# relays_1-4.net
KiCad netlist of a schematic drawn in Altium Designer
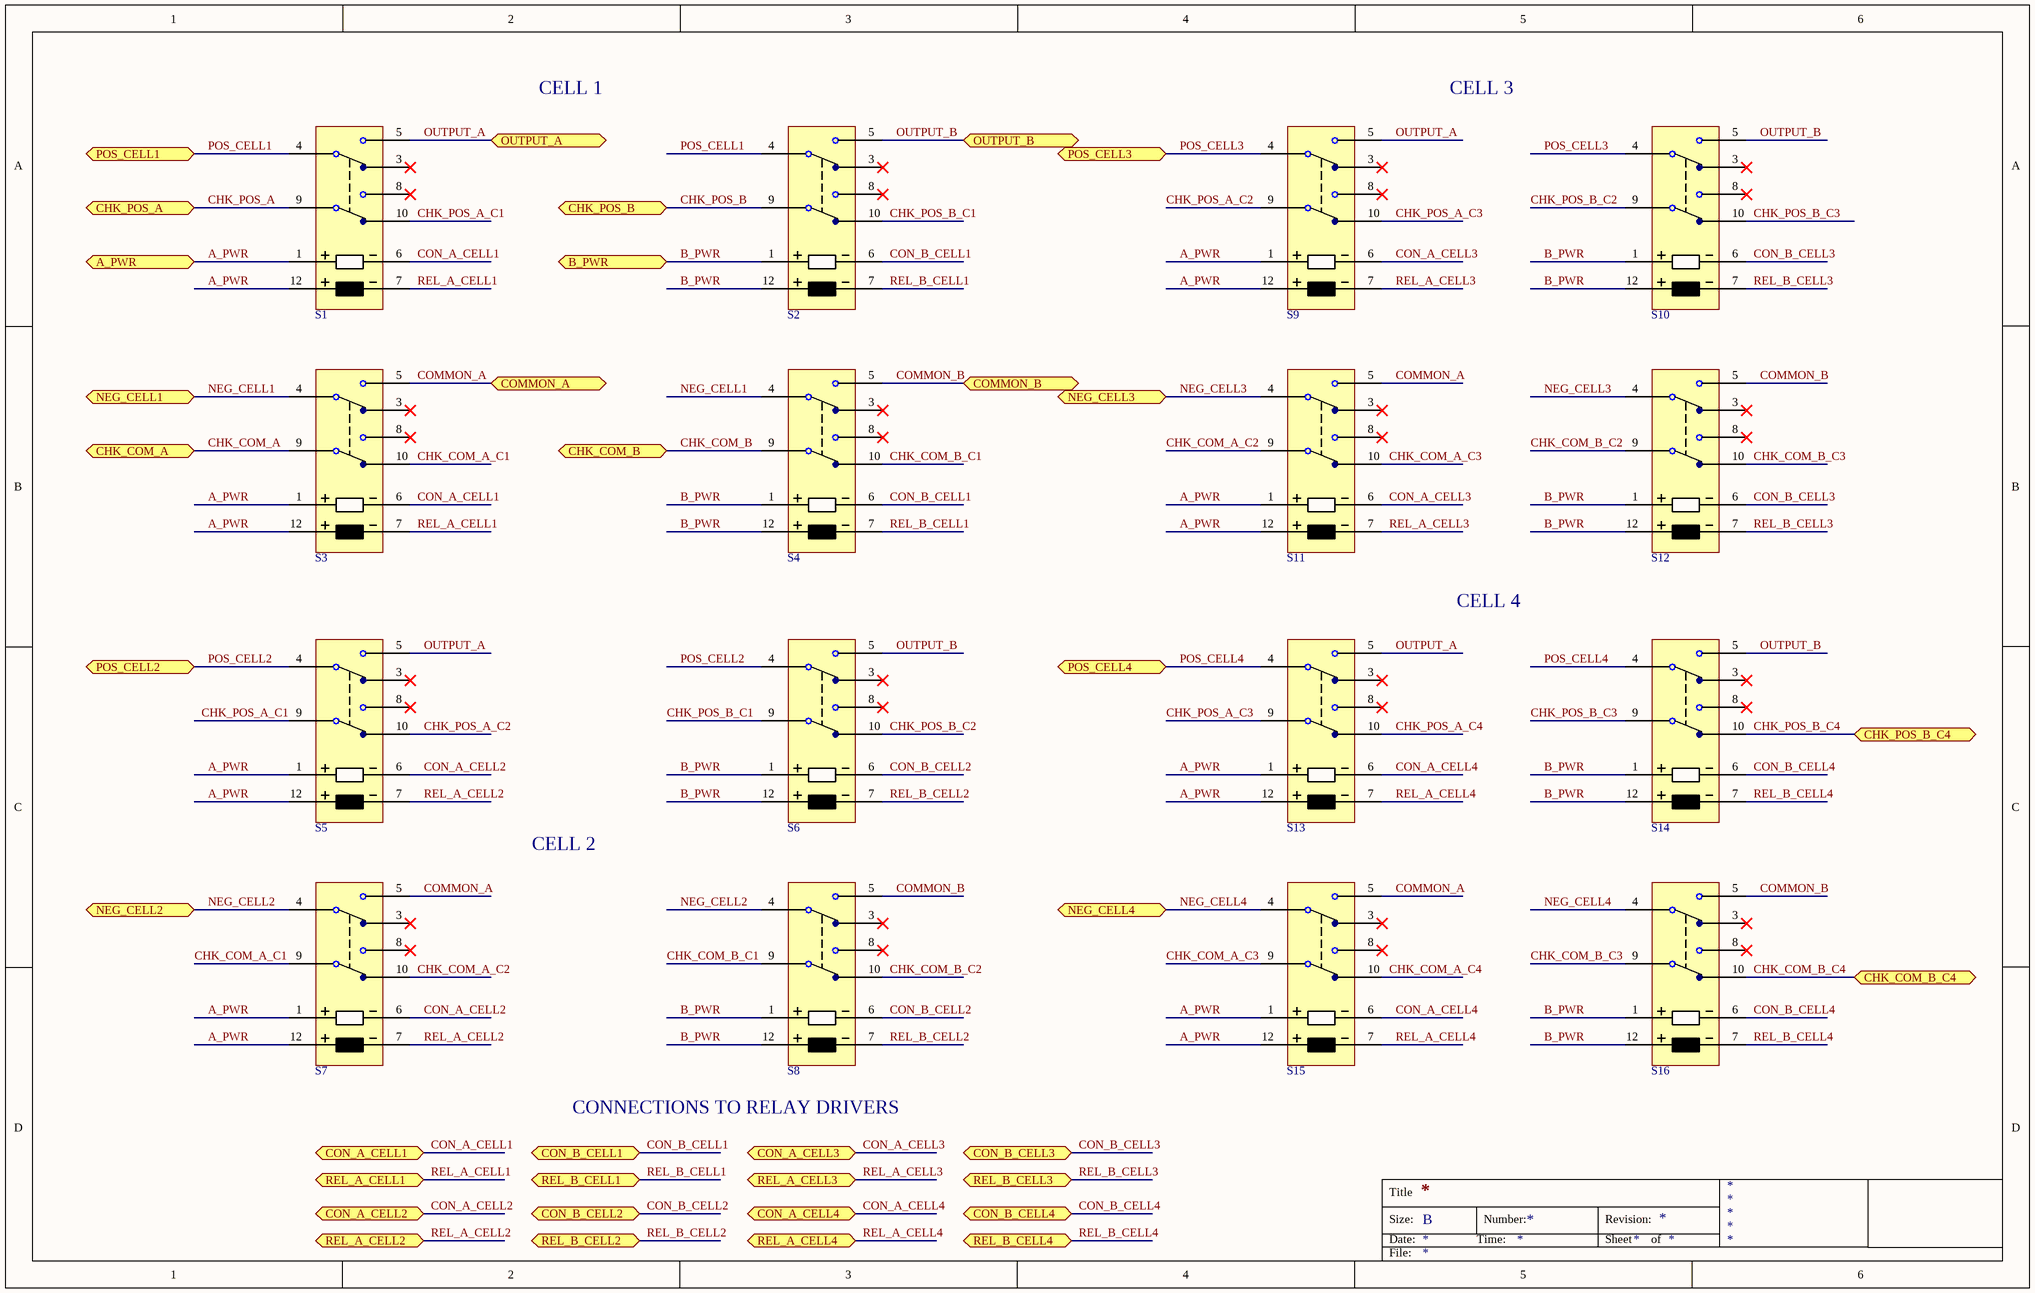
[diagram p0: relays_1-4.SchDoc]

(export (version "E")
  (design (tool "Eeschema 10.0.6"))
  (components
    (comp (ref "S1")
      (value "DPDT_RELAY_L2")
      (footprint "L2_RELAY")
      (description "RELAY GEN PURPOSE DPDT 1A 4.5V")
      (fields
        (field (name "MANUFACTURER") "Panasonic Electric Works")
        (field (name "MANUFACTURER PART NUMBER") "TXS2-L2-4.5V")
      )
      (libsource (lib "mechanart_oshw") (part "DPDT_RELAY_L2"))
    )
    (comp (ref "S2")
      (value "DPDT_RELAY_L2")
      (footprint "L2_RELAY")
      (description "RELAY GEN PURPOSE DPDT 1A 4.5V")
      (fields
        (field (name "MANUFACTURER") "Panasonic Electric Works")
        (field (name "MANUFACTURER PART NUMBER") "TXS2-L2-4.5V")
      )
      (libsource (lib "mechanart_oshw") (part "DPDT_RELAY_L2"))
    )
    (comp (ref "S3")
      (value "DPDT_RELAY_L2")
      (footprint "L2_RELAY")
      (description "RELAY GEN PURPOSE DPDT 1A 4.5V")
      (fields
        (field (name "MANUFACTURER") "Panasonic Electric Works")
        (field (name "MANUFACTURER PART NUMBER") "TXS2-L2-4.5V")
      )
      (libsource (lib "mechanart_oshw") (part "DPDT_RELAY_L2"))
    )
    (comp (ref "S4")
      (value "DPDT_RELAY_L2")
      (footprint "L2_RELAY")
      (description "RELAY GEN PURPOSE DPDT 1A 4.5V")
      (fields
        (field (name "MANUFACTURER") "Panasonic Electric Works")
        (field (name "MANUFACTURER PART NUMBER") "TXS2-L2-4.5V")
      )
      (libsource (lib "mechanart_oshw") (part "DPDT_RELAY_L2"))
    )
    (comp (ref "S5")
      (value "DPDT_RELAY_L2")
      (footprint "L2_RELAY")
      (description "RELAY GEN PURPOSE DPDT 1A 4.5V")
      (fields
        (field (name "MANUFACTURER") "Panasonic Electric Works")
        (field (name "MANUFACTURER PART NUMBER") "TXS2-L2-4.5V")
      )
      (libsource (lib "mechanart_oshw") (part "DPDT_RELAY_L2"))
    )
    (comp (ref "S6")
      (value "DPDT_RELAY_L2")
      (footprint "L2_RELAY")
      (description "RELAY GEN PURPOSE DPDT 1A 4.5V")
      (fields
        (field (name "MANUFACTURER") "Panasonic Electric Works")
        (field (name "MANUFACTURER PART NUMBER") "TXS2-L2-4.5V")
      )
      (libsource (lib "mechanart_oshw") (part "DPDT_RELAY_L2"))
    )
    (comp (ref "S7")
      (value "DPDT_RELAY_L2")
      (footprint "L2_RELAY")
      (description "RELAY GEN PURPOSE DPDT 1A 4.5V")
      (fields
        (field (name "MANUFACTURER") "Panasonic Electric Works")
        (field (name "MANUFACTURER PART NUMBER") "TXS2-L2-4.5V")
      )
      (libsource (lib "mechanart_oshw") (part "DPDT_RELAY_L2"))
    )
    (comp (ref "S8")
      (value "DPDT_RELAY_L2")
      (footprint "L2_RELAY")
      (description "RELAY GEN PURPOSE DPDT 1A 4.5V")
      (fields
        (field (name "MANUFACTURER") "Panasonic Electric Works")
        (field (name "MANUFACTURER PART NUMBER") "TXS2-L2-4.5V")
      )
      (libsource (lib "mechanart_oshw") (part "DPDT_RELAY_L2"))
    )
    (comp (ref "S9")
      (value "DPDT_RELAY_L2")
      (footprint "L2_RELAY")
      (description "RELAY GEN PURPOSE DPDT 1A 4.5V")
      (fields
        (field (name "MANUFACTURER") "Panasonic Electric Works")
        (field (name "MANUFACTURER PART NUMBER") "TXS2-L2-4.5V")
      )
      (libsource (lib "mechanart_oshw") (part "DPDT_RELAY_L2"))
    )
    (comp (ref "S10")
      (value "DPDT_RELAY_L2")
      (footprint "L2_RELAY")
      (description "RELAY GEN PURPOSE DPDT 1A 4.5V")
      (fields
        (field (name "MANUFACTURER") "Panasonic Electric Works")
        (field (name "MANUFACTURER PART NUMBER") "TXS2-L2-4.5V")
      )
      (libsource (lib "mechanart_oshw") (part "DPDT_RELAY_L2"))
    )
    (comp (ref "S11")
      (value "DPDT_RELAY_L2")
      (footprint "L2_RELAY")
      (description "RELAY GEN PURPOSE DPDT 1A 4.5V")
      (fields
        (field (name "MANUFACTURER") "Panasonic Electric Works")
        (field (name "MANUFACTURER PART NUMBER") "TXS2-L2-4.5V")
      )
      (libsource (lib "mechanart_oshw") (part "DPDT_RELAY_L2"))
    )
    (comp (ref "S12")
      (value "DPDT_RELAY_L2")
      (footprint "L2_RELAY")
      (description "RELAY GEN PURPOSE DPDT 1A 4.5V")
      (fields
        (field (name "MANUFACTURER") "Panasonic Electric Works")
        (field (name "MANUFACTURER PART NUMBER") "TXS2-L2-4.5V")
      )
      (libsource (lib "mechanart_oshw") (part "DPDT_RELAY_L2"))
    )
    (comp (ref "S13")
      (value "DPDT_RELAY_L2")
      (footprint "L2_RELAY")
      (description "RELAY GEN PURPOSE DPDT 1A 4.5V")
      (fields
        (field (name "MANUFACTURER") "Panasonic Electric Works")
        (field (name "MANUFACTURER PART NUMBER") "TXS2-L2-4.5V")
      )
      (libsource (lib "mechanart_oshw") (part "DPDT_RELAY_L2"))
    )
    (comp (ref "S14")
      (value "DPDT_RELAY_L2")
      (footprint "L2_RELAY")
      (description "RELAY GEN PURPOSE DPDT 1A 4.5V")
      (fields
        (field (name "MANUFACTURER") "Panasonic Electric Works")
        (field (name "MANUFACTURER PART NUMBER") "TXS2-L2-4.5V")
      )
      (libsource (lib "mechanart_oshw") (part "DPDT_RELAY_L2"))
    )
    (comp (ref "S15")
      (value "DPDT_RELAY_L2")
      (footprint "L2_RELAY")
      (description "RELAY GEN PURPOSE DPDT 1A 4.5V")
      (fields
        (field (name "MANUFACTURER") "Panasonic Electric Works")
        (field (name "MANUFACTURER PART NUMBER") "TXS2-L2-4.5V")
      )
      (libsource (lib "mechanart_oshw") (part "DPDT_RELAY_L2"))
    )
    (comp (ref "S16")
      (value "DPDT_RELAY_L2")
      (footprint "L2_RELAY")
      (description "RELAY GEN PURPOSE DPDT 1A 4.5V")
      (fields
        (field (name "MANUFACTURER") "Panasonic Electric Works")
        (field (name "MANUFACTURER PART NUMBER") "TXS2-L2-4.5V")
      )
      (libsource (lib "mechanart_oshw") (part "DPDT_RELAY_L2"))
    )
  )
  (nets
    (net (code "1") (name "/A_PWR") (class "Default")
      (node (ref "S1") (pin "1") (pinfunction "1_1") (pintype "passive"))
      (node (ref "S1") (pin "12") (pinfunction "12_12") (pintype "passive"))
      (node (ref "S11") (pin "1") (pinfunction "1_1") (pintype "passive"))
      (node (ref "S11") (pin "12") (pinfunction "12_12") (pintype "passive"))
      (node (ref "S13") (pin "1") (pinfunction "1_1") (pintype "passive"))
      (node (ref "S13") (pin "12") (pinfunction "12_12") (pintype "passive"))
      (node (ref "S15") (pin "1") (pinfunction "1_1") (pintype "passive"))
      (node (ref "S15") (pin "12") (pinfunction "12_12") (pintype "passive"))
      (node (ref "S3") (pin "1") (pinfunction "1_1") (pintype "passive"))
      (node (ref "S3") (pin "12") (pinfunction "12_12") (pintype "passive"))
      (node (ref "S5") (pin "1") (pinfunction "1_1") (pintype "passive"))
      (node (ref "S5") (pin "12") (pinfunction "12_12") (pintype "passive"))
      (node (ref "S7") (pin "1") (pinfunction "1_1") (pintype "passive"))
      (node (ref "S7") (pin "12") (pinfunction "12_12") (pintype "passive"))
      (node (ref "S9") (pin "1") (pinfunction "1_1") (pintype "passive"))
      (node (ref "S9") (pin "12") (pinfunction "12_12") (pintype "passive"))
    )
    (net (code "2") (name "/B_PWR") (class "Default")
      (node (ref "S10") (pin "1") (pinfunction "1_1") (pintype "passive"))
      (node (ref "S10") (pin "12") (pinfunction "12_12") (pintype "passive"))
      (node (ref "S12") (pin "1") (pinfunction "1_1") (pintype "passive"))
      (node (ref "S12") (pin "12") (pinfunction "12_12") (pintype "passive"))
      (node (ref "S14") (pin "1") (pinfunction "1_1") (pintype "passive"))
      (node (ref "S14") (pin "12") (pinfunction "12_12") (pintype "passive"))
      (node (ref "S16") (pin "1") (pinfunction "1_1") (pintype "passive"))
      (node (ref "S16") (pin "12") (pinfunction "12_12") (pintype "passive"))
      (node (ref "S2") (pin "1") (pinfunction "1_1") (pintype "passive"))
      (node (ref "S2") (pin "12") (pinfunction "12_12") (pintype "passive"))
      (node (ref "S4") (pin "1") (pinfunction "1_1") (pintype "passive"))
      (node (ref "S4") (pin "12") (pinfunction "12_12") (pintype "passive"))
      (node (ref "S6") (pin "1") (pinfunction "1_1") (pintype "passive"))
      (node (ref "S6") (pin "12") (pinfunction "12_12") (pintype "passive"))
      (node (ref "S8") (pin "1") (pinfunction "1_1") (pintype "passive"))
      (node (ref "S8") (pin "12") (pinfunction "12_12") (pintype "passive"))
    )
    (net (code "3") (name "/CHK_COM_A") (class "Default")
      (node (ref "S3") (pin "9") (pinfunction "9_9") (pintype "passive"))
    )
    (net (code "4") (name "/CHK_COM_A_C1") (class "Default")
      (node (ref "S3") (pin "10") (pinfunction "10_10") (pintype "passive"))
      (node (ref "S7") (pin "9") (pinfunction "9_9") (pintype "passive"))
    )
    (net (code "5") (name "/CHK_COM_A_C2") (class "Default")
      (node (ref "S11") (pin "9") (pinfunction "9_9") (pintype "passive"))
      (node (ref "S7") (pin "10") (pinfunction "10_10") (pintype "passive"))
    )
    (net (code "6") (name "/CHK_COM_A_C3") (class "Default")
      (node (ref "S11") (pin "10") (pinfunction "10_10") (pintype "passive"))
      (node (ref "S15") (pin "9") (pinfunction "9_9") (pintype "passive"))
    )
    (net (code "7") (name "/CHK_COM_A_C4") (class "Default")
      (node (ref "S15") (pin "10") (pinfunction "10_10") (pintype "passive"))
    )
    (net (code "8") (name "/CHK_COM_B") (class "Default")
      (node (ref "S4") (pin "9") (pinfunction "9_9") (pintype "passive"))
    )
    (net (code "9") (name "/CHK_COM_B_C1") (class "Default")
      (node (ref "S4") (pin "10") (pinfunction "10_10") (pintype "passive"))
      (node (ref "S8") (pin "9") (pinfunction "9_9") (pintype "passive"))
    )
    (net (code "10") (name "/CHK_COM_B_C2") (class "Default")
      (node (ref "S12") (pin "9") (pinfunction "9_9") (pintype "passive"))
      (node (ref "S8") (pin "10") (pinfunction "10_10") (pintype "passive"))
    )
    (net (code "11") (name "/CHK_COM_B_C3") (class "Default")
      (node (ref "S12") (pin "10") (pinfunction "10_10") (pintype "passive"))
      (node (ref "S16") (pin "9") (pinfunction "9_9") (pintype "passive"))
    )
    (net (code "12") (name "/CHK_COM_B_C4") (class "Default")
      (node (ref "S16") (pin "10") (pinfunction "10_10") (pintype "passive"))
    )
    (net (code "13") (name "/CHK_POS_A") (class "Default")
      (node (ref "S1") (pin "9") (pinfunction "9_9") (pintype "passive"))
    )
    (net (code "14") (name "/CHK_POS_A_C1") (class "Default")
      (node (ref "S1") (pin "10") (pinfunction "10_10") (pintype "passive"))
      (node (ref "S5") (pin "9") (pinfunction "9_9") (pintype "passive"))
    )
    (net (code "15") (name "/CHK_POS_A_C2") (class "Default")
      (node (ref "S5") (pin "10") (pinfunction "10_10") (pintype "passive"))
      (node (ref "S9") (pin "9") (pinfunction "9_9") (pintype "passive"))
    )
    (net (code "16") (name "/CHK_POS_A_C3") (class "Default")
      (node (ref "S13") (pin "9") (pinfunction "9_9") (pintype "passive"))
      (node (ref "S9") (pin "10") (pinfunction "10_10") (pintype "passive"))
    )
    (net (code "17") (name "/CHK_POS_A_C4") (class "Default")
      (node (ref "S13") (pin "10") (pinfunction "10_10") (pintype "passive"))
    )
    (net (code "18") (name "/CHK_POS_B") (class "Default")
      (node (ref "S2") (pin "9") (pinfunction "9_9") (pintype "passive"))
    )
    (net (code "19") (name "/CHK_POS_B_C1") (class "Default")
      (node (ref "S2") (pin "10") (pinfunction "10_10") (pintype "passive"))
      (node (ref "S6") (pin "9") (pinfunction "9_9") (pintype "passive"))
    )
    (net (code "20") (name "/CHK_POS_B_C2") (class "Default")
      (node (ref "S10") (pin "9") (pinfunction "9_9") (pintype "passive"))
      (node (ref "S6") (pin "10") (pinfunction "10_10") (pintype "passive"))
    )
    (net (code "21") (name "/CHK_POS_B_C3") (class "Default")
      (node (ref "S10") (pin "10") (pinfunction "10_10") (pintype "passive"))
      (node (ref "S14") (pin "9") (pinfunction "9_9") (pintype "passive"))
    )
    (net (code "22") (name "/CHK_POS_B_C4") (class "Default")
      (node (ref "S14") (pin "10") (pinfunction "10_10") (pintype "passive"))
    )
    (net (code "23") (name "/COMMON_A") (class "Default")
      (node (ref "S11") (pin "5") (pinfunction "5_5") (pintype "passive"))
      (node (ref "S15") (pin "5") (pinfunction "5_5") (pintype "passive"))
      (node (ref "S3") (pin "5") (pinfunction "5_5") (pintype "passive"))
      (node (ref "S7") (pin "5") (pinfunction "5_5") (pintype "passive"))
    )
    (net (code "24") (name "/COMMON_B") (class "Default")
      (node (ref "S12") (pin "5") (pinfunction "5_5") (pintype "passive"))
      (node (ref "S16") (pin "5") (pinfunction "5_5") (pintype "passive"))
      (node (ref "S4") (pin "5") (pinfunction "5_5") (pintype "passive"))
      (node (ref "S8") (pin "5") (pinfunction "5_5") (pintype "passive"))
    )
    (net (code "25") (name "/CON_A_CELL1") (class "Default")
      (node (ref "S1") (pin "6") (pinfunction "6_6") (pintype "passive"))
      (node (ref "S3") (pin "6") (pinfunction "6_6") (pintype "passive"))
    )
    (net (code "26") (name "/CON_A_CELL2") (class "Default")
      (node (ref "S5") (pin "6") (pinfunction "6_6") (pintype "passive"))
      (node (ref "S7") (pin "6") (pinfunction "6_6") (pintype "passive"))
    )
    (net (code "27") (name "/CON_A_CELL3") (class "Default")
      (node (ref "S11") (pin "6") (pinfunction "6_6") (pintype "passive"))
      (node (ref "S9") (pin "6") (pinfunction "6_6") (pintype "passive"))
    )
    (net (code "28") (name "/CON_A_CELL4") (class "Default")
      (node (ref "S13") (pin "6") (pinfunction "6_6") (pintype "passive"))
      (node (ref "S15") (pin "6") (pinfunction "6_6") (pintype "passive"))
    )
    (net (code "29") (name "/CON_B_CELL1") (class "Default")
      (node (ref "S2") (pin "6") (pinfunction "6_6") (pintype "passive"))
      (node (ref "S4") (pin "6") (pinfunction "6_6") (pintype "passive"))
    )
    (net (code "30") (name "/CON_B_CELL2") (class "Default")
      (node (ref "S6") (pin "6") (pinfunction "6_6") (pintype "passive"))
      (node (ref "S8") (pin "6") (pinfunction "6_6") (pintype "passive"))
    )
    (net (code "31") (name "/CON_B_CELL3") (class "Default")
      (node (ref "S10") (pin "6") (pinfunction "6_6") (pintype "passive"))
      (node (ref "S12") (pin "6") (pinfunction "6_6") (pintype "passive"))
    )
    (net (code "32") (name "/CON_B_CELL4") (class "Default")
      (node (ref "S14") (pin "6") (pinfunction "6_6") (pintype "passive"))
      (node (ref "S16") (pin "6") (pinfunction "6_6") (pintype "passive"))
    )
    (net (code "33") (name "/NEG_CELL1") (class "Default")
      (node (ref "S3") (pin "4") (pinfunction "4_4") (pintype "passive"))
      (node (ref "S4") (pin "4") (pinfunction "4_4") (pintype "passive"))
    )
    (net (code "34") (name "/NEG_CELL2") (class "Default")
      (node (ref "S7") (pin "4") (pinfunction "4_4") (pintype "passive"))
      (node (ref "S8") (pin "4") (pinfunction "4_4") (pintype "passive"))
    )
    (net (code "35") (name "/NEG_CELL3") (class "Default")
      (node (ref "S11") (pin "4") (pinfunction "4_4") (pintype "passive"))
      (node (ref "S12") (pin "4") (pinfunction "4_4") (pintype "passive"))
    )
    (net (code "36") (name "/NEG_CELL4") (class "Default")
      (node (ref "S15") (pin "4") (pinfunction "4_4") (pintype "passive"))
      (node (ref "S16") (pin "4") (pinfunction "4_4") (pintype "passive"))
    )
    (net (code "37") (name "/OUTPUT_A") (class "Default")
      (node (ref "S1") (pin "5") (pinfunction "5_5") (pintype "passive"))
      (node (ref "S13") (pin "5") (pinfunction "5_5") (pintype "passive"))
      (node (ref "S5") (pin "5") (pinfunction "5_5") (pintype "passive"))
      (node (ref "S9") (pin "5") (pinfunction "5_5") (pintype "passive"))
    )
    (net (code "38") (name "/OUTPUT_B") (class "Default")
      (node (ref "S10") (pin "5") (pinfunction "5_5") (pintype "passive"))
      (node (ref "S14") (pin "5") (pinfunction "5_5") (pintype "passive"))
      (node (ref "S2") (pin "5") (pinfunction "5_5") (pintype "passive"))
      (node (ref "S6") (pin "5") (pinfunction "5_5") (pintype "passive"))
    )
    (net (code "39") (name "/POS_CELL1") (class "Default")
      (node (ref "S1") (pin "4") (pinfunction "4_4") (pintype "passive"))
      (node (ref "S2") (pin "4") (pinfunction "4_4") (pintype "passive"))
    )
    (net (code "40") (name "/POS_CELL2") (class "Default")
      (node (ref "S5") (pin "4") (pinfunction "4_4") (pintype "passive"))
      (node (ref "S6") (pin "4") (pinfunction "4_4") (pintype "passive"))
    )
    (net (code "41") (name "/POS_CELL3") (class "Default")
      (node (ref "S10") (pin "4") (pinfunction "4_4") (pintype "passive"))
      (node (ref "S9") (pin "4") (pinfunction "4_4") (pintype "passive"))
    )
    (net (code "42") (name "/POS_CELL4") (class "Default")
      (node (ref "S13") (pin "4") (pinfunction "4_4") (pintype "passive"))
      (node (ref "S14") (pin "4") (pinfunction "4_4") (pintype "passive"))
    )
    (net (code "43") (name "/REL_A_CELL1") (class "Default")
      (node (ref "S1") (pin "7") (pinfunction "7_7") (pintype "passive"))
      (node (ref "S3") (pin "7") (pinfunction "7_7") (pintype "passive"))
    )
    (net (code "44") (name "/REL_A_CELL2") (class "Default")
      (node (ref "S5") (pin "7") (pinfunction "7_7") (pintype "passive"))
      (node (ref "S7") (pin "7") (pinfunction "7_7") (pintype "passive"))
    )
    (net (code "45") (name "/REL_A_CELL3") (class "Default")
      (node (ref "S11") (pin "7") (pinfunction "7_7") (pintype "passive"))
      (node (ref "S9") (pin "7") (pinfunction "7_7") (pintype "passive"))
    )
    (net (code "46") (name "/REL_A_CELL4") (class "Default")
      (node (ref "S13") (pin "7") (pinfunction "7_7") (pintype "passive"))
      (node (ref "S15") (pin "7") (pinfunction "7_7") (pintype "passive"))
    )
    (net (code "47") (name "/REL_B_CELL1") (class "Default")
      (node (ref "S2") (pin "7") (pinfunction "7_7") (pintype "passive"))
      (node (ref "S4") (pin "7") (pinfunction "7_7") (pintype "passive"))
    )
    (net (code "48") (name "/REL_B_CELL2") (class "Default")
      (node (ref "S6") (pin "7") (pinfunction "7_7") (pintype "passive"))
      (node (ref "S8") (pin "7") (pinfunction "7_7") (pintype "passive"))
    )
    (net (code "49") (name "/REL_B_CELL3") (class "Default")
      (node (ref "S10") (pin "7") (pinfunction "7_7") (pintype "passive"))
      (node (ref "S12") (pin "7") (pinfunction "7_7") (pintype "passive"))
    )
    (net (code "50") (name "/REL_B_CELL4") (class "Default")
      (node (ref "S14") (pin "7") (pinfunction "7_7") (pintype "passive"))
      (node (ref "S16") (pin "7") (pinfunction "7_7") (pintype "passive"))
    )
    (net (code "51") (name "unconnected-(S1-Pad3)") (class "Default")
      (node (ref "S1") (pin "3") (pinfunction "3_3") (pintype "passive+no_connect"))
    )
    (net (code "52") (name "unconnected-(S1-Pad8)") (class "Default")
      (node (ref "S1") (pin "8") (pinfunction "8_8") (pintype "passive+no_connect"))
    )
    (net (code "53") (name "unconnected-(S2-Pad3)") (class "Default")
      (node (ref "S2") (pin "3") (pinfunction "3_3") (pintype "passive+no_connect"))
    )
    (net (code "54") (name "unconnected-(S2-Pad8)") (class "Default")
      (node (ref "S2") (pin "8") (pinfunction "8_8") (pintype "passive+no_connect"))
    )
    (net (code "55") (name "unconnected-(S3-Pad3)") (class "Default")
      (node (ref "S3") (pin "3") (pinfunction "3_3") (pintype "passive+no_connect"))
    )
    (net (code "56") (name "unconnected-(S3-Pad8)") (class "Default")
      (node (ref "S3") (pin "8") (pinfunction "8_8") (pintype "passive+no_connect"))
    )
    (net (code "57") (name "unconnected-(S4-Pad3)") (class "Default")
      (node (ref "S4") (pin "3") (pinfunction "3_3") (pintype "passive+no_connect"))
    )
    (net (code "58") (name "unconnected-(S4-Pad8)") (class "Default")
      (node (ref "S4") (pin "8") (pinfunction "8_8") (pintype "passive+no_connect"))
    )
    (net (code "59") (name "unconnected-(S5-Pad3)") (class "Default")
      (node (ref "S5") (pin "3") (pinfunction "3_3") (pintype "passive+no_connect"))
    )
    (net (code "60") (name "unconnected-(S5-Pad8)") (class "Default")
      (node (ref "S5") (pin "8") (pinfunction "8_8") (pintype "passive+no_connect"))
    )
    (net (code "61") (name "unconnected-(S6-Pad3)") (class "Default")
      (node (ref "S6") (pin "3") (pinfunction "3_3") (pintype "passive+no_connect"))
    )
    (net (code "62") (name "unconnected-(S6-Pad8)") (class "Default")
      (node (ref "S6") (pin "8") (pinfunction "8_8") (pintype "passive+no_connect"))
    )
    (net (code "63") (name "unconnected-(S7-Pad3)") (class "Default")
      (node (ref "S7") (pin "3") (pinfunction "3_3") (pintype "passive+no_connect"))
    )
    (net (code "64") (name "unconnected-(S7-Pad8)") (class "Default")
      (node (ref "S7") (pin "8") (pinfunction "8_8") (pintype "passive+no_connect"))
    )
    (net (code "65") (name "unconnected-(S8-Pad3)") (class "Default")
      (node (ref "S8") (pin "3") (pinfunction "3_3") (pintype "passive+no_connect"))
    )
    (net (code "66") (name "unconnected-(S8-Pad8)") (class "Default")
      (node (ref "S8") (pin "8") (pinfunction "8_8") (pintype "passive+no_connect"))
    )
    (net (code "67") (name "unconnected-(S9-Pad3)") (class "Default")
      (node (ref "S9") (pin "3") (pinfunction "3_3") (pintype "passive+no_connect"))
    )
    (net (code "68") (name "unconnected-(S9-Pad8)") (class "Default")
      (node (ref "S9") (pin "8") (pinfunction "8_8") (pintype "passive+no_connect"))
    )
    (net (code "69") (name "unconnected-(S10-Pad3)") (class "Default")
      (node (ref "S10") (pin "3") (pinfunction "3_3") (pintype "passive+no_connect"))
    )
    (net (code "70") (name "unconnected-(S10-Pad8)") (class "Default")
      (node (ref "S10") (pin "8") (pinfunction "8_8") (pintype "passive+no_connect"))
    )
    (net (code "71") (name "unconnected-(S11-Pad3)") (class "Default")
      (node (ref "S11") (pin "3") (pinfunction "3_3") (pintype "passive+no_connect"))
    )
    (net (code "72") (name "unconnected-(S11-Pad8)") (class "Default")
      (node (ref "S11") (pin "8") (pinfunction "8_8") (pintype "passive+no_connect"))
    )
    (net (code "73") (name "unconnected-(S12-Pad3)") (class "Default")
      (node (ref "S12") (pin "3") (pinfunction "3_3") (pintype "passive+no_connect"))
    )
    (net (code "74") (name "unconnected-(S12-Pad8)") (class "Default")
      (node (ref "S12") (pin "8") (pinfunction "8_8") (pintype "passive+no_connect"))
    )
    (net (code "75") (name "unconnected-(S13-Pad3)") (class "Default")
      (node (ref "S13") (pin "3") (pinfunction "3_3") (pintype "passive+no_connect"))
    )
    (net (code "76") (name "unconnected-(S13-Pad8)") (class "Default")
      (node (ref "S13") (pin "8") (pinfunction "8_8") (pintype "passive+no_connect"))
    )
    (net (code "77") (name "unconnected-(S14-Pad3)") (class "Default")
      (node (ref "S14") (pin "3") (pinfunction "3_3") (pintype "passive+no_connect"))
    )
    (net (code "78") (name "unconnected-(S14-Pad8)") (class "Default")
      (node (ref "S14") (pin "8") (pinfunction "8_8") (pintype "passive+no_connect"))
    )
    (net (code "79") (name "unconnected-(S15-Pad3)") (class "Default")
      (node (ref "S15") (pin "3") (pinfunction "3_3") (pintype "passive+no_connect"))
    )
    (net (code "80") (name "unconnected-(S15-Pad8)") (class "Default")
      (node (ref "S15") (pin "8") (pinfunction "8_8") (pintype "passive+no_connect"))
    )
    (net (code "81") (name "unconnected-(S16-Pad3)") (class "Default")
      (node (ref "S16") (pin "3") (pinfunction "3_3") (pintype "passive+no_connect"))
    )
    (net (code "82") (name "unconnected-(S16-Pad8)") (class "Default")
      (node (ref "S16") (pin "8") (pinfunction "8_8") (pintype "passive+no_connect"))
    )
  )
)
